# PC.net
KiCad netlist of a schematic drawn in Altium Designer
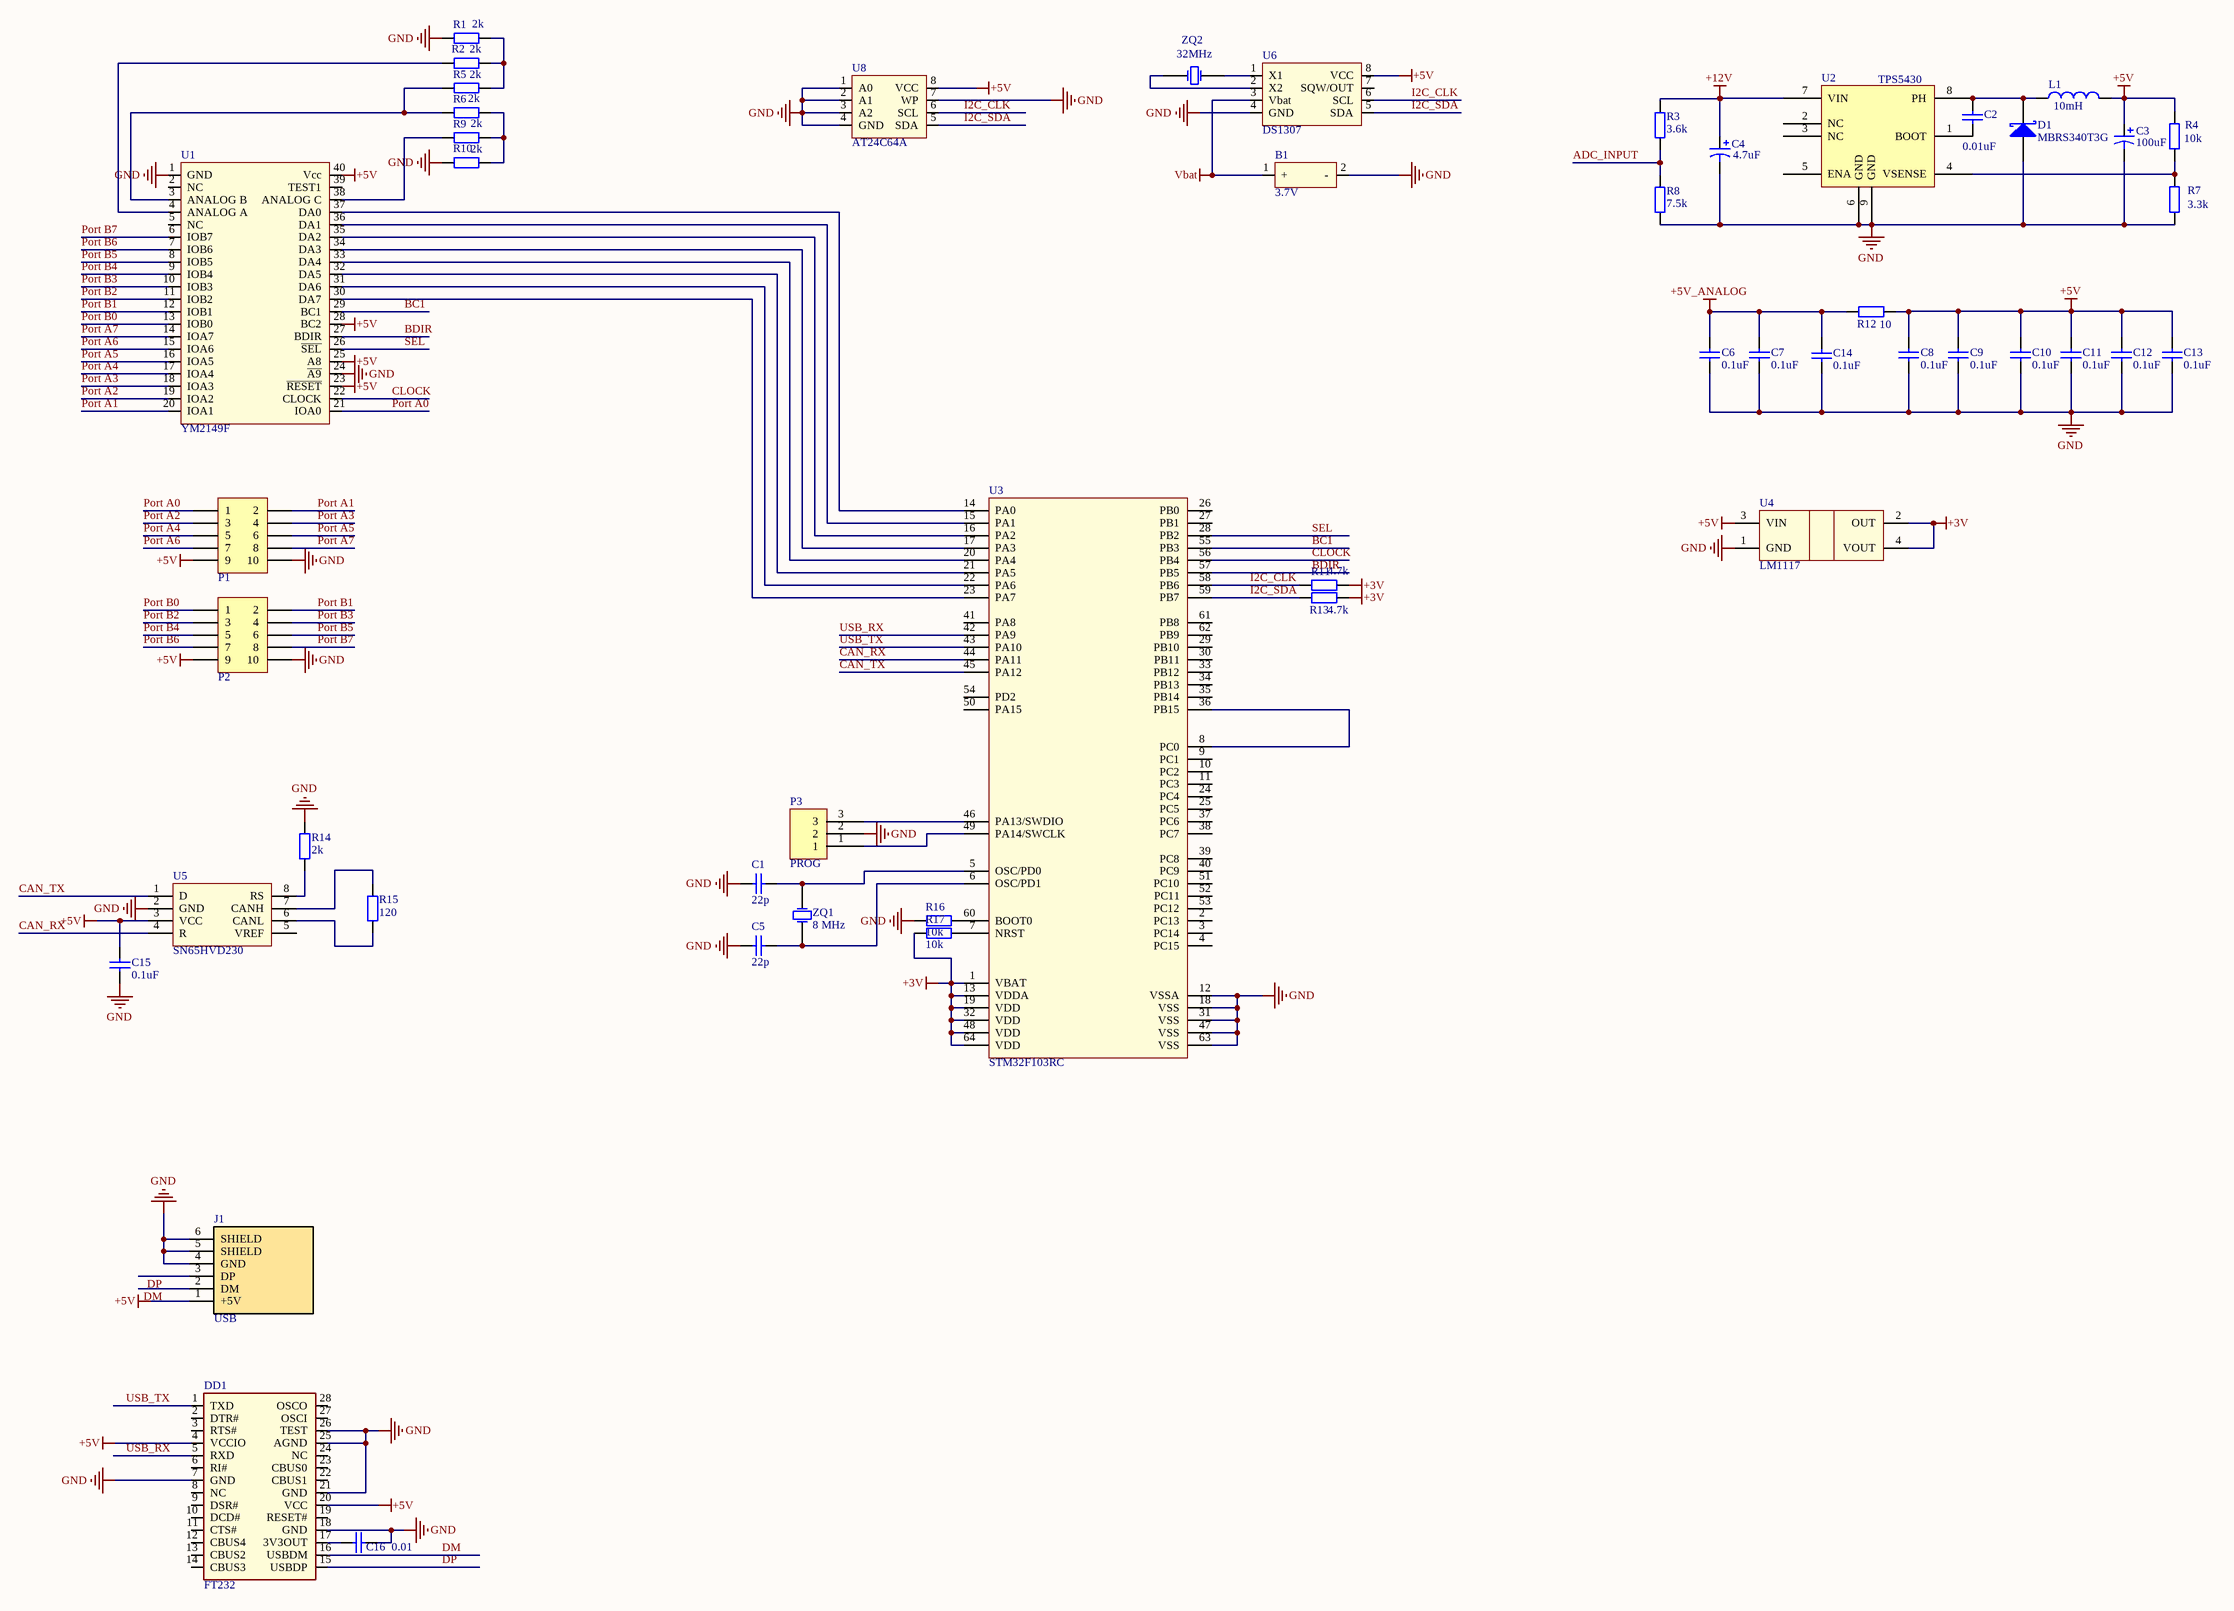
[diagram p0: PC.SchDoc]

(export (version "E")
  (design (tool "Eeschema 10.0.6"))
  (components
    (comp (ref "B1")
      (value "3.7V")
      (footprint "OnePlate:Battery")
      (libsource (lib "OnePlate") (part "Battery"))
    )
    (comp (ref "C1")
      (value "22p")
      (footprint "OnePlate:Capacitor 0603")
      (description "Capacitor")
      (libsource (lib "OnePlate") (part "Capacitor"))
    )
    (comp (ref "C2")
      (value "0.01uF")
      (footprint "CAP 0805")
      (description "Capacitor")
      (libsource (lib "MyCustomLib") (part "Capacitor"))
    )
    (comp (ref "C3")
      (value "100uF")
      (footprint "OnePlate:Capacitor D case")
      (description "Polarized Capacitor (Axial)")
      (fields (field (name "PUBLISHER") "Altium Limited"))
      (libsource (lib "MyCustomLib") (part "Cap Pol"))
    )
    (comp (ref "C4")
      (value "4.7uF")
      (footprint "OnePlate:Capacitor D case")
      (description "Polarized Capacitor (Axial)")
      (fields (field (name "PUBLISHER") "Altium Limited"))
      (libsource (lib "MyCustomLib") (part "Cap Pol"))
    )
    (comp (ref "C5")
      (value "22p")
      (footprint "OnePlate:Capacitor 0603")
      (description "Capacitor")
      (libsource (lib "OnePlate") (part "Capacitor"))
    )
    (comp (ref "C6")
      (value "0.1uF")
      (footprint "CAP 0805")
      (description "Capacitor")
      (libsource (lib "OnePlate") (part "Capacitor"))
    )
    (comp (ref "C7")
      (value "0.1uF")
      (footprint "CAP 0805")
      (description "Capacitor")
      (libsource (lib "OnePlate") (part "Capacitor"))
    )
    (comp (ref "C8")
      (value "0.1uF")
      (footprint "CAP 0805")
      (description "Capacitor")
      (libsource (lib "OnePlate") (part "Capacitor"))
    )
    (comp (ref "C9")
      (value "0.1uF")
      (footprint "CAP 0805")
      (description "Capacitor")
      (libsource (lib "OnePlate") (part "Capacitor"))
    )
    (comp (ref "C10")
      (value "0.1uF")
      (footprint "CAP 0805")
      (description "Capacitor")
      (libsource (lib "OnePlate") (part "Capacitor"))
    )
    (comp (ref "C11")
      (value "0.1uF")
      (footprint "CAP 0805")
      (description "Capacitor")
      (libsource (lib "OnePlate") (part "Capacitor"))
    )
    (comp (ref "C12")
      (value "0.1uF")
      (footprint "CAP 0805")
      (description "Capacitor")
      (libsource (lib "OnePlate") (part "Capacitor"))
    )
    (comp (ref "C13")
      (value "0.1uF")
      (footprint "CAP 0805")
      (description "Capacitor")
      (libsource (lib "OnePlate") (part "Capacitor"))
    )
    (comp (ref "C14")
      (value "0.1uF")
      (footprint "CAP 0805")
      (description "Capacitor")
      (libsource (lib "OnePlate") (part "Capacitor"))
    )
    (comp (ref "C15")
      (value "0.1uF")
      (footprint "OnePlate:Capacitor 0603")
      (description "Capacitor")
      (libsource (lib "OnePlate") (part "Capacitor"))
    )
    (comp (ref "C16")
      (value "0.01")
      (footprint "OnePlate:0805")
      (description "Capacitor")
      (libsource (lib "OnePlate") (part "Capacitor"))
    )
    (comp (ref "D1")
      (value "MBRS340T3G")
      (footprint "OnePlate:SMC")
      (description "Schottky Rectifier")
      (fields (field (name "PUBLISHER") "Altium Limited"))
      (libsource (lib "MyCustomLib") (part "Diode schottky"))
    )
    (comp (ref "DD1")
      (value "FT232")
      (footprint "OnePlate:SSOP28")
      (libsource (lib "OnePlate") (part "FT232"))
    )
    (comp (ref "J1")
      (value "USB")
      (footprint "OnePlate:USB2.5-2H4D - 2")
      (libsource (lib "OnePlate") (part "USB"))
    )
    (comp (ref "L1")
      (value "10mH")
      (footprint "OnePlate:B82477")
      (description "Inductor")
      (fields (field (name "PUBLISHER") "Altium Limited"))
      (libsource (lib "MyCustomLib") (part "Inductor"))
    )
    (comp (ref "P1")
      (value "Header 5X2")
      (footprint "OnePlate:HDR2X5")
      (description "Header, 5-Pin, Dual row")
      (fields (field (name "PUBLISHER") "Altium Limited"))
      (libsource (lib "OnePlate") (part "Header 5X2"))
    )
    (comp (ref "P2")
      (value "Header 5X2")
      (footprint "OnePlate:HDR2X5")
      (description "Header, 5-Pin, Dual row")
      (fields (field (name "PUBLISHER") "Altium Limited"))
      (libsource (lib "OnePlate") (part "Header 5X2"))
    )
    (comp (ref "P3")
      (value "PROG")
      (footprint "OnePlate:Header 3pin 2.54")
      (libsource (lib "OnePlate") (part "Header1x3"))
    )
    (comp (ref "R1")
      (value "2k")
      (footprint "OnePlate:RES 0603")
      (libsource (lib "OnePlate") (part "Resistor"))
    )
    (comp (ref "R2")
      (value "2k")
      (footprint "OnePlate:RES 0603")
      (libsource (lib "OnePlate") (part "Resistor"))
    )
    (comp (ref "R3") (value "3.6k") (footprint "RES 0805") (libsource (lib "OnePlate") (part "Resistor")))
    (comp (ref "R4") (value "10k") (footprint "RES 0805") (libsource (lib "MyCustomLib") (part "Resistor")))
    (comp (ref "R5")
      (value "2k")
      (footprint "OnePlate:RES 0603")
      (libsource (lib "OnePlate") (part "Resistor"))
    )
    (comp (ref "R6")
      (value "2k")
      (footprint "OnePlate:RES 0603")
      (libsource (lib "OnePlate") (part "Resistor"))
    )
    (comp (ref "R7") (value "3.3k") (footprint "RES 0805") (libsource (lib "MyCustomLib") (part "Resistor")))
    (comp (ref "R8") (value "7.5k") (footprint "RES 0805") (libsource (lib "OnePlate") (part "Resistor")))
    (comp (ref "R9")
      (value "2k")
      (footprint "OnePlate:RES 0603")
      (libsource (lib "OnePlate") (part "Resistor"))
    )
    (comp (ref "R10")
      (value "2k")
      (footprint "OnePlate:RES 0603")
      (libsource (lib "OnePlate") (part "Resistor"))
    )
    (comp (ref "R11")
      (value "4.7k")
      (footprint "OnePlate:RES 0603")
      (libsource (lib "OnePlate") (part "Resistor"))
    )
    (comp (ref "R12") (value "10") (footprint "RES 0805") (libsource (lib "OnePlate") (part "Resistor")))
    (comp (ref "R13")
      (value "4.7k")
      (footprint "OnePlate:RES 0603")
      (libsource (lib "OnePlate") (part "Resistor"))
    )
    (comp (ref "R14")
      (value "2k")
      (footprint "OnePlate:RES 0603")
      (libsource (lib "OnePlate") (part "Resistor"))
    )
    (comp (ref "R15")
      (value "120")
      (footprint "OnePlate:RES 0603")
      (libsource (lib "OnePlate") (part "Resistor"))
    )
    (comp (ref "R16")
      (value "10k")
      (footprint "OnePlate:RES 0603")
      (libsource (lib "OnePlate") (part "Resistor"))
    )
    (comp (ref "R17")
      (value "10k")
      (footprint "OnePlate:RES 0603")
      (libsource (lib "OnePlate") (part "Resistor"))
    )
    (comp (ref "U1")
      (value "YM2149F")
      (footprint "OnePlate:DIP40")
      (libsource (lib "OnePlate") (part "YM2149F"))
    )
    (comp (ref "U2")
      (value "TPS5430")
      (footprint "OnePlate:PSOP8")
      (description "tps5430")
      (libsource (lib "MyCustomLib") (part "TPS5430"))
    )
    (comp (ref "U3")
      (value "STM32F103RC")
      (footprint "OnePlate:LQFP64_L")
      (libsource (lib "OnePlate") (part "STM32F103RC"))
    )
    (comp (ref "U4")
      (value "LM1117")
      (footprint "OnePlate:SOT-223 - 2")
      (description "Linear regulator")
      (libsource (lib "OnePlate") (part "LM1117"))
    )
    (comp (ref "U5")
      (value "SN65HVD230")
      (footprint "OnePlate:SO-8")
      (description "CAN PHY")
      (libsource (lib "OnePlate") (part "SN65HVD230"))
    )
    (comp (ref "U6")
      (value "DS1307")
      (footprint "OnePlate:SO-8")
      (libsource (lib "OnePlate") (part "DS1307"))
    )
    (comp (ref "U8")
      (value "AT24C64A")
      (footprint "OnePlate:SO-8")
      (libsource (lib "OnePlate") (part "AT24C64A"))
    )
    (comp (ref "ZQ1") (value "8 MHz") (footprint "OnePlate:QZ") (libsource (lib "OnePlate") (part "QZ")))
    (comp (ref "ZQ2") (value "32MHz") (footprint "OnePlate:Quartz") (libsource (lib "OnePlate") (part "QZ")))
  )
  (nets
    (net (code "1") (name "+3V") (class "Default")
      (node (ref "R11") (pin "2") (pinfunction "2_2") (pintype "passive"))
      (node (ref "R13") (pin "2") (pinfunction "2_2") (pintype "passive"))
      (node (ref "R17") (pin "1") (pinfunction "1_1") (pintype "passive"))
      (node (ref "U3") (pin "1") (pinfunction "VBAT_1") (pintype "passive"))
      (node (ref "U3") (pin "13") (pinfunction "VDDA_13") (pintype "passive"))
      (node (ref "U3") (pin "19") (pinfunction "VDD_19") (pintype "passive"))
      (node (ref "U3") (pin "32") (pinfunction "VDD_32") (pintype "passive"))
      (node (ref "U3") (pin "48") (pinfunction "VDD_48") (pintype "passive"))
      (node (ref "U3") (pin "64") (pinfunction "VDD_64") (pintype "passive"))
      (node (ref "U4") (pin "2") (pinfunction "OUT_2") (pintype "passive"))
      (node (ref "U4") (pin "4") (pinfunction "VOUT_4") (pintype "passive"))
    )
    (net (code "2") (name "+5V") (class "Default")
      (node (ref "C10") (pin "2") (pinfunction "2_2") (pintype "passive"))
      (node (ref "C11") (pin "2") (pinfunction "2_2") (pintype "passive"))
      (node (ref "C12") (pin "2") (pinfunction "2_2") (pintype "passive"))
      (node (ref "C13") (pin "2") (pinfunction "2_2") (pintype "passive"))
      (node (ref "C15") (pin "2") (pinfunction "2_2") (pintype "passive"))
      (node (ref "C3") (pin "1") (pinfunction "1_1") (pintype "passive"))
      (node (ref "C8") (pin "2") (pinfunction "2_2") (pintype "passive"))
      (node (ref "C9") (pin "2") (pinfunction "2_2") (pintype "passive"))
      (node (ref "DD1") (pin "20") (pinfunction "VCC_20") (pintype "passive"))
      (node (ref "DD1") (pin "4") (pinfunction "VCCIO_4") (pintype "passive"))
      (node (ref "J1") (pin "1") (pinfunction "+5V_1") (pintype "passive"))
      (node (ref "L1") (pin "2") (pinfunction "2_2") (pintype "passive"))
      (node (ref "P1") (pin "9") (pinfunction "9_9") (pintype "passive"))
      (node (ref "P2") (pin "9") (pinfunction "9_9") (pintype "passive"))
      (node (ref "R12") (pin "2") (pinfunction "2_2") (pintype "passive"))
      (node (ref "R4") (pin "2") (pinfunction "2_2") (pintype "passive"))
      (node (ref "U1") (pin "23") (pinfunction "~{RESET}_23") (pintype "passive"))
      (node (ref "U1") (pin "25") (pinfunction "A8_25") (pintype "passive"))
      (node (ref "U1") (pin "28") (pinfunction "BC2_28") (pintype "passive"))
      (node (ref "U1") (pin "40") (pinfunction "Vcc_40") (pintype "passive"))
      (node (ref "U4") (pin "3") (pinfunction "VIN_3") (pintype "passive"))
      (node (ref "U5") (pin "3") (pinfunction "VCC_3") (pintype "passive"))
      (node (ref "U6") (pin "8") (pinfunction "VCC_8") (pintype "passive"))
      (node (ref "U8") (pin "8") (pinfunction "VCC_8") (pintype "passive"))
    )
    (net (code "3") (name "+5V_ANALOG") (class "Default")
      (node (ref "C14") (pin "1") (pinfunction "1_1") (pintype "passive"))
      (node (ref "C6") (pin "2") (pinfunction "2_2") (pintype "passive"))
      (node (ref "C7") (pin "2") (pinfunction "2_2") (pintype "passive"))
      (node (ref "R12") (pin "1") (pinfunction "1_1") (pintype "passive"))
    )
    (net (code "4") (name "+12V") (class "Default")
      (node (ref "C4") (pin "1") (pinfunction "1_1") (pintype "passive"))
      (node (ref "R3") (pin "2") (pinfunction "2_2") (pintype "passive"))
      (node (ref "U2") (pin "7") (pinfunction "VIN_7") (pintype "passive"))
    )
    (net (code "5") (name "/ADC_INPUT") (class "Default")
      (node (ref "R3") (pin "1") (pinfunction "1_1") (pintype "passive"))
      (node (ref "R8") (pin "2") (pinfunction "2_2") (pintype "passive"))
    )
    (net (code "6") (name "/BC1") (class "Default")
      (node (ref "U1") (pin "29") (pinfunction "BC1_29") (pintype "passive"))
      (node (ref "U3") (pin "55") (pinfunction "PB3_55") (pintype "passive"))
    )
    (net (code "7") (name "/BDIR") (class "Default")
      (node (ref "U1") (pin "27") (pinfunction "BDIR_27") (pintype "passive"))
      (node (ref "U3") (pin "57") (pinfunction "PB5_57") (pintype "passive"))
    )
    (net (code "8") (name "/CAN_RX") (class "Default")
      (node (ref "U3") (pin "44") (pinfunction "PA11_44") (pintype "passive"))
      (node (ref "U5") (pin "4") (pinfunction "R_4") (pintype "passive"))
    )
    (net (code "9") (name "/CAN_TX") (class "Default")
      (node (ref "U3") (pin "45") (pinfunction "PA12_45") (pintype "passive"))
      (node (ref "U5") (pin "1") (pinfunction "D_1") (pintype "passive"))
    )
    (net (code "10") (name "/CLOCK") (class "Default")
      (node (ref "U1") (pin "22") (pinfunction "CLOCK_22") (pintype "passive"))
      (node (ref "U3") (pin "56") (pinfunction "PB4_56") (pintype "passive"))
    )
    (net (code "11") (name "/DM") (class "Default")
      (node (ref "DD1") (pin "16") (pinfunction "USBDM_16") (pintype "passive"))
      (node (ref "J1") (pin "2") (pinfunction "DM_2") (pintype "passive"))
    )
    (net (code "12") (name "/DP") (class "Default")
      (node (ref "DD1") (pin "15") (pinfunction "USBDP_15") (pintype "passive"))
      (node (ref "J1") (pin "3") (pinfunction "DP_3") (pintype "passive"))
    )
    (net (code "13") (name "/I2C_CLK") (class "Default")
      (node (ref "R11") (pin "1") (pinfunction "1_1") (pintype "passive"))
      (node (ref "U3") (pin "58") (pinfunction "PB6_58") (pintype "passive"))
      (node (ref "U6") (pin "6") (pinfunction "SCL_6") (pintype "passive"))
      (node (ref "U8") (pin "6") (pinfunction "SCL_6") (pintype "passive"))
    )
    (net (code "14") (name "/I2C_SDA") (class "Default")
      (node (ref "R13") (pin "1") (pinfunction "1_1") (pintype "passive"))
      (node (ref "U3") (pin "59") (pinfunction "PB7_59") (pintype "passive"))
      (node (ref "U6") (pin "5") (pinfunction "SDA_5") (pintype "passive"))
      (node (ref "U8") (pin "5") (pinfunction "SDA_5") (pintype "passive"))
    )
    (net (code "15") (name "/Port A0") (class "Default")
      (node (ref "P1") (pin "1") (pinfunction "1_1") (pintype "passive"))
      (node (ref "U1") (pin "21") (pinfunction "IOA0_21") (pintype "passive"))
    )
    (net (code "16") (name "/Port A1") (class "Default")
      (node (ref "P1") (pin "2") (pinfunction "2_2") (pintype "passive"))
      (node (ref "U1") (pin "20") (pinfunction "IOA1_20") (pintype "passive"))
    )
    (net (code "17") (name "/Port A2") (class "Default")
      (node (ref "P1") (pin "3") (pinfunction "3_3") (pintype "passive"))
      (node (ref "U1") (pin "19") (pinfunction "IOA2_19") (pintype "passive"))
    )
    (net (code "18") (name "/Port A3") (class "Default")
      (node (ref "P1") (pin "4") (pinfunction "4_4") (pintype "passive"))
      (node (ref "U1") (pin "18") (pinfunction "IOA3_18") (pintype "passive"))
    )
    (net (code "19") (name "/Port A4") (class "Default")
      (node (ref "P1") (pin "5") (pinfunction "5_5") (pintype "passive"))
      (node (ref "U1") (pin "17") (pinfunction "IOA4_17") (pintype "passive"))
    )
    (net (code "20") (name "/Port A5") (class "Default")
      (node (ref "P1") (pin "6") (pinfunction "6_6") (pintype "passive"))
      (node (ref "U1") (pin "16") (pinfunction "IOA5_16") (pintype "passive"))
    )
    (net (code "21") (name "/Port A6") (class "Default")
      (node (ref "P1") (pin "7") (pinfunction "7_7") (pintype "passive"))
      (node (ref "U1") (pin "15") (pinfunction "IOA6_15") (pintype "passive"))
    )
    (net (code "22") (name "/Port A7") (class "Default")
      (node (ref "P1") (pin "8") (pinfunction "8_8") (pintype "passive"))
      (node (ref "U1") (pin "14") (pinfunction "IOA7_14") (pintype "passive"))
    )
    (net (code "23") (name "/Port B0") (class "Default")
      (node (ref "P2") (pin "1") (pinfunction "1_1") (pintype "passive"))
      (node (ref "U1") (pin "13") (pinfunction "IOB0_13") (pintype "passive"))
    )
    (net (code "24") (name "/Port B1") (class "Default")
      (node (ref "P2") (pin "2") (pinfunction "2_2") (pintype "passive"))
      (node (ref "U1") (pin "12") (pinfunction "IOB1_12") (pintype "passive"))
    )
    (net (code "25") (name "/Port B2") (class "Default")
      (node (ref "P2") (pin "3") (pinfunction "3_3") (pintype "passive"))
      (node (ref "U1") (pin "11") (pinfunction "IOB2_11") (pintype "passive"))
    )
    (net (code "26") (name "/Port B3") (class "Default")
      (node (ref "P2") (pin "4") (pinfunction "4_4") (pintype "passive"))
      (node (ref "U1") (pin "10") (pinfunction "IOB3_10") (pintype "passive"))
    )
    (net (code "27") (name "/Port B4") (class "Default")
      (node (ref "P2") (pin "5") (pinfunction "5_5") (pintype "passive"))
      (node (ref "U1") (pin "9") (pinfunction "IOB4_9") (pintype "passive"))
    )
    (net (code "28") (name "/Port B5") (class "Default")
      (node (ref "P2") (pin "6") (pinfunction "6_6") (pintype "passive"))
      (node (ref "U1") (pin "8") (pinfunction "IOB5_8") (pintype "passive"))
    )
    (net (code "29") (name "/Port B6") (class "Default")
      (node (ref "P2") (pin "7") (pinfunction "7_7") (pintype "passive"))
      (node (ref "U1") (pin "7") (pinfunction "IOB6_7") (pintype "passive"))
    )
    (net (code "30") (name "/Port B7") (class "Default")
      (node (ref "P2") (pin "8") (pinfunction "8_8") (pintype "passive"))
      (node (ref "U1") (pin "6") (pinfunction "IOB7_6") (pintype "passive"))
    )
    (net (code "31") (name "/SEL") (class "Default")
      (node (ref "U1") (pin "26") (pinfunction "~{SEL}_26") (pintype "passive"))
      (node (ref "U3") (pin "28") (pinfunction "PB2_28") (pintype "passive"))
    )
    (net (code "32") (name "/USB_RX") (class "Default")
      (node (ref "DD1") (pin "5") (pinfunction "RXD_5") (pintype "passive"))
      (node (ref "U3") (pin "42") (pinfunction "PA9_42") (pintype "passive"))
    )
    (net (code "33") (name "/USB_TX") (class "Default")
      (node (ref "DD1") (pin "1") (pinfunction "TXD_1") (pintype "passive"))
      (node (ref "U3") (pin "43") (pinfunction "PA10_43") (pintype "passive"))
    )
    (net (code "34") (name "GND") (class "Default")
      (node (ref "B1") (pin "2") (pinfunction "-_2") (pintype "passive"))
      (node (ref "C1") (pin "1") (pinfunction "1_1") (pintype "passive"))
      (node (ref "C10") (pin "1") (pinfunction "1_1") (pintype "passive"))
      (node (ref "C11") (pin "1") (pinfunction "1_1") (pintype "passive"))
      (node (ref "C12") (pin "1") (pinfunction "1_1") (pintype "passive"))
      (node (ref "C13") (pin "1") (pinfunction "1_1") (pintype "passive"))
      (node (ref "C14") (pin "2") (pinfunction "2_2") (pintype "passive"))
      (node (ref "C15") (pin "1") (pinfunction "1_1") (pintype "passive"))
      (node (ref "C16") (pin "1") (pinfunction "1_1") (pintype "passive"))
      (node (ref "C3") (pin "2") (pinfunction "2_2") (pintype "passive"))
      (node (ref "C4") (pin "2") (pinfunction "2_2") (pintype "passive"))
      (node (ref "C5") (pin "1") (pinfunction "1_1") (pintype "passive"))
      (node (ref "C6") (pin "1") (pinfunction "1_1") (pintype "passive"))
      (node (ref "C7") (pin "1") (pinfunction "1_1") (pintype "passive"))
      (node (ref "C8") (pin "1") (pinfunction "1_1") (pintype "passive"))
      (node (ref "C9") (pin "1") (pinfunction "1_1") (pintype "passive"))
      (node (ref "D1") (pin "2") (pinfunction "A_2") (pintype "passive"))
      (node (ref "DD1") (pin "18") (pinfunction "GND_18") (pintype "passive"))
      (node (ref "DD1") (pin "21") (pinfunction "GND_21") (pintype "passive"))
      (node (ref "DD1") (pin "25") (pinfunction "AGND_25") (pintype "passive"))
      (node (ref "DD1") (pin "26") (pinfunction "TEST_26") (pintype "passive"))
      (node (ref "DD1") (pin "7") (pinfunction "GND_7") (pintype "passive"))
      (node (ref "J1") (pin "4") (pinfunction "GND_4") (pintype "passive"))
      (node (ref "J1") (pin "5") (pinfunction "SHIELD_5") (pintype "passive"))
      (node (ref "J1") (pin "6") (pinfunction "SHIELD_6") (pintype "passive"))
      (node (ref "P1") (pin "10") (pinfunction "10_10") (pintype "passive"))
      (node (ref "P2") (pin "10") (pinfunction "10_10") (pintype "passive"))
      (node (ref "P3") (pin "2") (pinfunction "2_2") (pintype "passive"))
      (node (ref "R1") (pin "1") (pinfunction "1_1") (pintype "passive"))
      (node (ref "R10") (pin "1") (pinfunction "1_1") (pintype "passive"))
      (node (ref "R14") (pin "2") (pinfunction "2_2") (pintype "passive"))
      (node (ref "R16") (pin "1") (pinfunction "1_1") (pintype "passive"))
      (node (ref "R7") (pin "1") (pinfunction "1_1") (pintype "passive"))
      (node (ref "R8") (pin "1") (pinfunction "1_1") (pintype "passive"))
      (node (ref "U1") (pin "1") (pinfunction "GND_1") (pintype "passive"))
      (node (ref "U1") (pin "24") (pinfunction "~{A9}_24") (pintype "passive"))
      (node (ref "U2") (pin "6") (pinfunction "GND_6") (pintype "passive"))
      (node (ref "U2") (pin "9") (pinfunction "GND_9") (pintype "passive"))
      (node (ref "U3") (pin "12") (pinfunction "VSSA_12") (pintype "passive"))
      (node (ref "U3") (pin "18") (pinfunction "VSS_18") (pintype "passive"))
      (node (ref "U3") (pin "31") (pinfunction "VSS_31") (pintype "passive"))
      (node (ref "U3") (pin "47") (pinfunction "VSS_47") (pintype "passive"))
      (node (ref "U3") (pin "63") (pinfunction "VSS_63") (pintype "passive"))
      (node (ref "U4") (pin "1") (pinfunction "GND_1") (pintype "passive"))
      (node (ref "U5") (pin "2") (pinfunction "GND_2") (pintype "passive"))
      (node (ref "U6") (pin "4") (pinfunction "GND_4") (pintype "passive"))
      (node (ref "U8") (pin "1") (pinfunction "A0_1") (pintype "passive"))
      (node (ref "U8") (pin "2") (pinfunction "A1_2") (pintype "passive"))
      (node (ref "U8") (pin "3") (pinfunction "A2_3") (pintype "passive"))
      (node (ref "U8") (pin "4") (pinfunction "GND_4") (pintype "passive"))
      (node (ref "U8") (pin "7") (pinfunction "WP_7") (pintype "passive"))
    )
    (net (code "35") (name "Net-(D1-K)") (class "Default")
      (node (ref "C2") (pin "2") (pinfunction "2_2") (pintype "passive"))
      (node (ref "D1") (pin "1") (pinfunction "K_1") (pintype "passive"))
      (node (ref "L1") (pin "1") (pinfunction "1_1") (pintype "passive"))
      (node (ref "U2") (pin "8") (pinfunction "PH_8") (pintype "passive"))
    )
    (net (code "36") (name "Net-(DD1-3V3OUT)") (class "Default")
      (node (ref "C16") (pin "2") (pinfunction "2_2") (pintype "passive"))
      (node (ref "DD1") (pin "17") (pinfunction "3V3OUT_17") (pintype "passive"))
    )
    (net (code "37") (name "Net-(R1-Pad2)") (class "Default")
      (node (ref "R1") (pin "2") (pinfunction "2_2") (pintype "passive"))
      (node (ref "R2") (pin "2") (pinfunction "2_2") (pintype "passive"))
      (node (ref "R5") (pin "2") (pinfunction "2_2") (pintype "passive"))
    )
    (net (code "38") (name "Net-(R10-Pad2)") (class "Default")
      (node (ref "R10") (pin "2") (pinfunction "2_2") (pintype "passive"))
      (node (ref "R6") (pin "2") (pinfunction "2_2") (pintype "passive"))
      (node (ref "R9") (pin "2") (pinfunction "2_2") (pintype "passive"))
    )
    (net (code "39") (name "Net-(U1-ANALOG_A)") (class "Default")
      (node (ref "R2") (pin "1") (pinfunction "1_1") (pintype "passive"))
      (node (ref "U1") (pin "4") (pinfunction "ANALOG_A_4") (pintype "passive"))
    )
    (net (code "40") (name "Net-(U1-ANALOG_B)") (class "Default")
      (node (ref "R5") (pin "1") (pinfunction "1_1") (pintype "passive"))
      (node (ref "R6") (pin "1") (pinfunction "1_1") (pintype "passive"))
      (node (ref "U1") (pin "3") (pinfunction "ANALOG_B_3") (pintype "passive"))
    )
    (net (code "41") (name "Net-(U1-ANALOG_C)") (class "Default")
      (node (ref "R9") (pin "1") (pinfunction "1_1") (pintype "passive"))
      (node (ref "U1") (pin "38") (pinfunction "ANALOG_C_38") (pintype "passive"))
    )
    (net (code "42") (name "Net-(U1-DA0)") (class "Default")
      (node (ref "U1") (pin "37") (pinfunction "DA0_37") (pintype "passive"))
      (node (ref "U3") (pin "14") (pinfunction "PA0_14") (pintype "passive"))
    )
    (net (code "43") (name "Net-(U1-DA1)") (class "Default")
      (node (ref "U1") (pin "36") (pinfunction "DA1_36") (pintype "passive"))
      (node (ref "U3") (pin "15") (pinfunction "PA1_15") (pintype "passive"))
    )
    (net (code "44") (name "Net-(U1-DA2)") (class "Default")
      (node (ref "U1") (pin "35") (pinfunction "DA2_35") (pintype "passive"))
      (node (ref "U3") (pin "16") (pinfunction "PA2_16") (pintype "passive"))
    )
    (net (code "45") (name "Net-(U1-DA3)") (class "Default")
      (node (ref "U1") (pin "34") (pinfunction "DA3_34") (pintype "passive"))
      (node (ref "U3") (pin "17") (pinfunction "PA3_17") (pintype "passive"))
    )
    (net (code "46") (name "Net-(U1-DA4)") (class "Default")
      (node (ref "U1") (pin "33") (pinfunction "DA4_33") (pintype "passive"))
      (node (ref "U3") (pin "20") (pinfunction "PA4_20") (pintype "passive"))
    )
    (net (code "47") (name "Net-(U1-DA5)") (class "Default")
      (node (ref "U1") (pin "32") (pinfunction "DA5_32") (pintype "passive"))
      (node (ref "U3") (pin "21") (pinfunction "PA5_21") (pintype "passive"))
    )
    (net (code "48") (name "Net-(U1-DA6)") (class "Default")
      (node (ref "U1") (pin "31") (pinfunction "DA6_31") (pintype "passive"))
      (node (ref "U3") (pin "22") (pinfunction "PA6_22") (pintype "passive"))
    )
    (net (code "49") (name "Net-(U1-DA7)") (class "Default")
      (node (ref "U1") (pin "30") (pinfunction "DA7_30") (pintype "passive"))
      (node (ref "U3") (pin "23") (pinfunction "PA7_23") (pintype "passive"))
    )
    (net (code "50") (name "Net-(U2-BOOT)") (class "Default")
      (node (ref "C2") (pin "1") (pinfunction "1_1") (pintype "passive"))
      (node (ref "U2") (pin "1") (pinfunction "BOOT_1") (pintype "passive"))
    )
    (net (code "51") (name "Net-(U2-VSENSE)") (class "Default")
      (node (ref "R4") (pin "1") (pinfunction "1_1") (pintype "passive"))
      (node (ref "R7") (pin "2") (pinfunction "2_2") (pintype "passive"))
      (node (ref "U2") (pin "4") (pinfunction "VSENSE_4") (pintype "passive"))
    )
    (net (code "52") (name "Net-(U3-BOOT0)") (class "Default")
      (node (ref "R16") (pin "2") (pinfunction "2_2") (pintype "passive"))
      (node (ref "U3") (pin "60") (pinfunction "BOOT0_60") (pintype "passive"))
    )
    (net (code "53") (name "Net-(U3-NRST)") (class "Default")
      (node (ref "R17") (pin "2") (pinfunction "2_2") (pintype "passive"))
      (node (ref "U3") (pin "7") (pinfunction "NRST_7") (pintype "passive"))
    )
    (net (code "54") (name "Net-(U3-OSC{slash}PD0)") (class "Default")
      (node (ref "C1") (pin "2") (pinfunction "2_2") (pintype "passive"))
      (node (ref "U3") (pin "5") (pinfunction "OSC/PD0_5") (pintype "passive"))
      (node (ref "ZQ1") (pin "2") (pinfunction "OSC2_2") (pintype "passive"))
    )
    (net (code "55") (name "Net-(U3-OSC{slash}PD1)") (class "Default")
      (node (ref "C5") (pin "2") (pinfunction "2_2") (pintype "passive"))
      (node (ref "U3") (pin "6") (pinfunction "OSC/PD1_6") (pintype "passive"))
      (node (ref "ZQ1") (pin "1") (pinfunction "OSC1_1") (pintype "passive"))
    )
    (net (code "56") (name "Net-(U3-PA13{slash}SWDIO)") (class "Default")
      (node (ref "P3") (pin "3") (pinfunction "3_3") (pintype "passive"))
      (node (ref "U3") (pin "46") (pinfunction "PA13/SWDIO_46") (pintype "passive"))
    )
    (net (code "57") (name "Net-(U3-PA14{slash}SWCLK)") (class "Default")
      (node (ref "P3") (pin "1") (pinfunction "1_1") (pintype "passive"))
      (node (ref "U3") (pin "49") (pinfunction "PA14/SWCLK_49") (pintype "passive"))
    )
    (net (code "58") (name "Net-(U3-PB15)") (class "Default")
      (node (ref "U3") (pin "36") (pinfunction "PB15_36") (pintype "passive"))
      (node (ref "U3") (pin "8") (pinfunction "PC0_8") (pintype "passive"))
    )
    (net (code "59") (name "Net-(U5-CANH)") (class "Default")
      (node (ref "R15") (pin "2") (pinfunction "2_2") (pintype "passive"))
      (node (ref "U5") (pin "7") (pinfunction "CANH_7") (pintype "passive"))
    )
    (net (code "60") (name "Net-(U5-CANL)") (class "Default")
      (node (ref "R15") (pin "1") (pinfunction "1_1") (pintype "passive"))
      (node (ref "U5") (pin "6") (pinfunction "CANL_6") (pintype "passive"))
    )
    (net (code "61") (name "Net-(U5-RS)") (class "Default")
      (node (ref "R14") (pin "1") (pinfunction "1_1") (pintype "passive"))
      (node (ref "U5") (pin "8") (pinfunction "RS_8") (pintype "passive"))
    )
    (net (code "62") (name "Net-(U6-X1)") (class "Default")
      (node (ref "U6") (pin "1") (pinfunction "X1_1") (pintype "passive"))
      (node (ref "ZQ2") (pin "1") (pinfunction "OSC1_1") (pintype "passive"))
    )
    (net (code "63") (name "Net-(U6-X2)") (class "Default")
      (node (ref "U6") (pin "2") (pinfunction "X2_2") (pintype "passive"))
      (node (ref "ZQ2") (pin "2") (pinfunction "OSC2_2") (pintype "passive"))
    )
    (net (code "64") (name "Vbat") (class "Default")
      (node (ref "B1") (pin "1") (pinfunction "+_1") (pintype "passive"))
      (node (ref "U6") (pin "3") (pinfunction "Vbat_3") (pintype "passive"))
    )
    (net (code "65") (name "unconnected-(DD1-CBUS0-Pad23)") (class "Default")
      (node (ref "DD1") (pin "23") (pinfunction "CBUS0_23") (pintype "passive"))
    )
    (net (code "66") (name "unconnected-(DD1-CBUS1-Pad22)") (class "Default")
      (node (ref "DD1") (pin "22") (pinfunction "CBUS1_22") (pintype "passive"))
    )
    (net (code "67") (name "unconnected-(DD1-CBUS2-Pad13)") (class "Default")
      (node (ref "DD1") (pin "13") (pinfunction "CBUS2_13") (pintype "passive"))
    )
    (net (code "68") (name "unconnected-(DD1-CBUS3-Pad14)") (class "Default")
      (node (ref "DD1") (pin "14") (pinfunction "CBUS3_14") (pintype "passive"))
    )
    (net (code "69") (name "unconnected-(DD1-CBUS4-Pad12)") (class "Default")
      (node (ref "DD1") (pin "12") (pinfunction "CBUS4_12") (pintype "passive"))
    )
    (net (code "70") (name "unconnected-(DD1-CTS#-Pad11)") (class "Default")
      (node (ref "DD1") (pin "11") (pinfunction "CTS#_11") (pintype "passive"))
    )
    (net (code "71") (name "unconnected-(DD1-DCD#-Pad10)") (class "Default")
      (node (ref "DD1") (pin "10") (pinfunction "DCD#_10") (pintype "passive"))
    )
    (net (code "72") (name "unconnected-(DD1-DSR#-Pad9)") (class "Default")
      (node (ref "DD1") (pin "9") (pinfunction "DSR#_9") (pintype "passive"))
    )
    (net (code "73") (name "unconnected-(DD1-DTR#-Pad2)") (class "Default")
      (node (ref "DD1") (pin "2") (pinfunction "DTR#_2") (pintype "passive"))
    )
    (net (code "74") (name "unconnected-(DD1-NC-Pad8)") (class "Default")
      (node (ref "DD1") (pin "8") (pinfunction "NC_8") (pintype "passive"))
    )
    (net (code "75") (name "unconnected-(DD1-NC-Pad24)") (class "Default")
      (node (ref "DD1") (pin "24") (pinfunction "NC_24") (pintype "passive"))
    )
    (net (code "76") (name "unconnected-(DD1-OSCI-Pad27)") (class "Default")
      (node (ref "DD1") (pin "27") (pinfunction "OSCI_27") (pintype "passive"))
    )
    (net (code "77") (name "unconnected-(DD1-OSCO-Pad28)") (class "Default")
      (node (ref "DD1") (pin "28") (pinfunction "OSCO_28") (pintype "passive"))
    )
    (net (code "78") (name "unconnected-(DD1-RESET#-Pad19)") (class "Default")
      (node (ref "DD1") (pin "19") (pinfunction "RESET#_19") (pintype "passive"))
    )
    (net (code "79") (name "unconnected-(DD1-RI#-Pad6)") (class "Default")
      (node (ref "DD1") (pin "6") (pinfunction "RI#_6") (pintype "passive"))
    )
    (net (code "80") (name "unconnected-(DD1-RTS#-Pad3)") (class "Default")
      (node (ref "DD1") (pin "3") (pinfunction "RTS#_3") (pintype "passive"))
    )
    (net (code "81") (name "unconnected-(U1-NC-Pad2)") (class "Default")
      (node (ref "U1") (pin "2") (pinfunction "NC_2") (pintype "passive"))
    )
    (net (code "82") (name "unconnected-(U1-NC-Pad5)") (class "Default")
      (node (ref "U1") (pin "5") (pinfunction "NC_5") (pintype "passive"))
    )
    (net (code "83") (name "unconnected-(U1-TEST1-Pad39)") (class "Default")
      (node (ref "U1") (pin "39") (pinfunction "TEST1_39") (pintype "passive"))
    )
    (net (code "84") (name "unconnected-(U2-ENA-Pad5)") (class "Default")
      (node (ref "U2") (pin "5") (pinfunction "ENA_5") (pintype "passive"))
    )
    (net (code "85") (name "unconnected-(U2-NC-Pad2)") (class "Default")
      (node (ref "U2") (pin "2") (pinfunction "NC_2") (pintype "passive"))
    )
    (net (code "86") (name "unconnected-(U2-NC-Pad3)") (class "Default")
      (node (ref "U2") (pin "3") (pinfunction "NC_3") (pintype "passive"))
    )
    (net (code "87") (name "unconnected-(U3-PA8-Pad41)") (class "Default")
      (node (ref "U3") (pin "41") (pinfunction "PA8_41") (pintype "passive"))
    )
    (net (code "88") (name "unconnected-(U3-PA15-Pad50)") (class "Default")
      (node (ref "U3") (pin "50") (pinfunction "PA15_50") (pintype "passive"))
    )
    (net (code "89") (name "unconnected-(U3-PB0-Pad26)") (class "Default")
      (node (ref "U3") (pin "26") (pinfunction "PB0_26") (pintype "passive"))
    )
    (net (code "90") (name "unconnected-(U3-PB1-Pad27)") (class "Default")
      (node (ref "U3") (pin "27") (pinfunction "PB1_27") (pintype "passive"))
    )
    (net (code "91") (name "unconnected-(U3-PB8-Pad61)") (class "Default")
      (node (ref "U3") (pin "61") (pinfunction "PB8_61") (pintype "passive"))
    )
    (net (code "92") (name "unconnected-(U3-PB9-Pad62)") (class "Default")
      (node (ref "U3") (pin "62") (pinfunction "PB9_62") (pintype "passive"))
    )
    (net (code "93") (name "unconnected-(U3-PB10-Pad29)") (class "Default")
      (node (ref "U3") (pin "29") (pinfunction "PB10_29") (pintype "passive"))
    )
    (net (code "94") (name "unconnected-(U3-PB11-Pad30)") (class "Default")
      (node (ref "U3") (pin "30") (pinfunction "PB11_30") (pintype "passive"))
    )
    (net (code "95") (name "unconnected-(U3-PB12-Pad33)") (class "Default")
      (node (ref "U3") (pin "33") (pinfunction "PB12_33") (pintype "passive"))
    )
    (net (code "96") (name "unconnected-(U3-PB13-Pad34)") (class "Default")
      (node (ref "U3") (pin "34") (pinfunction "PB13_34") (pintype "passive"))
    )
    (net (code "97") (name "unconnected-(U3-PB14-Pad35)") (class "Default")
      (node (ref "U3") (pin "35") (pinfunction "PB14_35") (pintype "passive"))
    )
    (net (code "98") (name "unconnected-(U3-PC1-Pad9)") (class "Default")
      (node (ref "U3") (pin "9") (pinfunction "PC1_9") (pintype "passive"))
    )
    (net (code "99") (name "unconnected-(U3-PC2-Pad10)") (class "Default")
      (node (ref "U3") (pin "10") (pinfunction "PC2_10") (pintype "passive"))
    )
    (net (code "100") (name "unconnected-(U3-PC3-Pad11)") (class "Default")
      (node (ref "U3") (pin "11") (pinfunction "PC3_11") (pintype "passive"))
    )
    (net (code "101") (name "unconnected-(U3-PC4-Pad24)") (class "Default")
      (node (ref "U3") (pin "24") (pinfunction "PC4_24") (pintype "passive"))
    )
    (net (code "102") (name "unconnected-(U3-PC5-Pad25)") (class "Default")
      (node (ref "U3") (pin "25") (pinfunction "PC5_25") (pintype "passive"))
    )
    (net (code "103") (name "unconnected-(U3-PC6-Pad37)") (class "Default")
      (node (ref "U3") (pin "37") (pinfunction "PC6_37") (pintype "passive"))
    )
    (net (code "104") (name "unconnected-(U3-PC7-Pad38)") (class "Default")
      (node (ref "U3") (pin "38") (pinfunction "PC7_38") (pintype "passive"))
    )
    (net (code "105") (name "unconnected-(U3-PC8-Pad39)") (class "Default")
      (node (ref "U3") (pin "39") (pinfunction "PC8_39") (pintype "passive"))
    )
    (net (code "106") (name "unconnected-(U3-PC9-Pad40)") (class "Default")
      (node (ref "U3") (pin "40") (pinfunction "PC9_40") (pintype "passive"))
    )
    (net (code "107") (name "unconnected-(U3-PC10-Pad51)") (class "Default")
      (node (ref "U3") (pin "51") (pinfunction "PC10_51") (pintype "passive"))
    )
    (net (code "108") (name "unconnected-(U3-PC11-Pad52)") (class "Default")
      (node (ref "U3") (pin "52") (pinfunction "PC11_52") (pintype "passive"))
    )
    (net (code "109") (name "unconnected-(U3-PC12-Pad53)") (class "Default")
      (node (ref "U3") (pin "53") (pinfunction "PC12_53") (pintype "passive"))
    )
    (net (code "110") (name "unconnected-(U3-PC13-Pad2)") (class "Default")
      (node (ref "U3") (pin "2") (pinfunction "PC13_2") (pintype "passive"))
    )
    (net (code "111") (name "unconnected-(U3-PC14-Pad3)") (class "Default")
      (node (ref "U3") (pin "3") (pinfunction "PC14_3") (pintype "passive"))
    )
    (net (code "112") (name "unconnected-(U3-PC15-Pad4)") (class "Default")
      (node (ref "U3") (pin "4") (pinfunction "PC15_4") (pintype "passive"))
    )
    (net (code "113") (name "unconnected-(U3-PD2-Pad54)") (class "Default")
      (node (ref "U3") (pin "54") (pinfunction "PD2_54") (pintype "passive"))
    )
    (net (code "114") (name "unconnected-(U5-VREF-Pad5)") (class "Default")
      (node (ref "U5") (pin "5") (pinfunction "VREF_5") (pintype "passive"))
    )
    (net (code "115") (name "unconnected-(U6-SQW{slash}OUT-Pad7)") (class "Default")
      (node (ref "U6") (pin "7") (pinfunction "SQW/OUT_7") (pintype "passive"))
    )
  )
)
